# 03_-_CPU_-_SIGNAL_USB_JTAG.net
KiCad netlist of a schematic drawn in Altium Designer
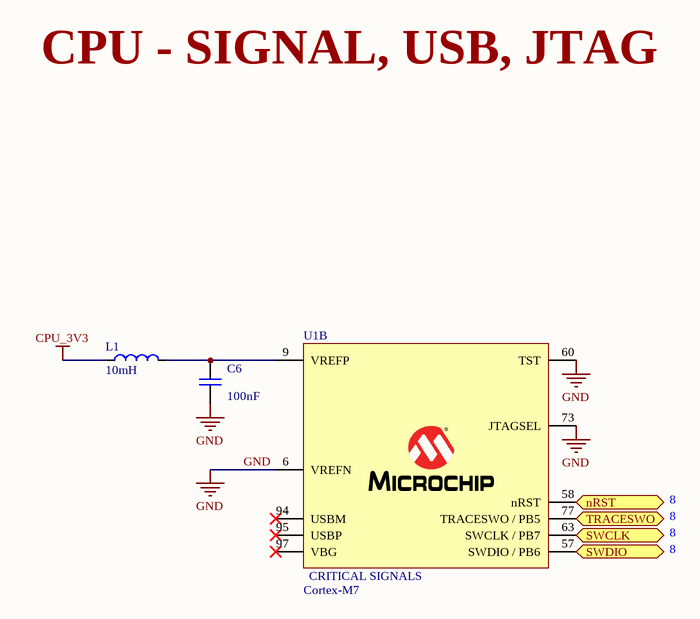
[diagram p0: [03] - CPU - SIGNAL, USB, JTAG.SchDoc]

(export (version "E")
  (design (tool "Eeschema 10.0.6"))
  (components
    (comp (ref "C6")
      (value "100nF")
      (footprint "C0603")
      (description "C0603")
      (fields (field (name "Comment") "02016D104KAT2A"))
      (libsource (lib "Passive components") (part "02016D104KAT2A"))
    )
    (comp (ref "L1")
      (value "10mH")
      (footprint "Inductor 0603")
      (description "Inductor 0603")
      (fields (field (name "Comment") "MLZ1608A2R2WT"))
      (libsource (lib "Passive components") (part "MLZ1608A2R2WT"))
    )
    (comp (ref "U1")
      (value "Cortex-M7")
      (footprint "ATSAMS70N19A-AN")
      (description "ATSAMS70N19")
      (libsource (lib "Microcontrollers") (part "ATSAMS70N19A-AN"))
    )
  )
  (nets
    (net (code "1") (name "/SWCLK") (class "Default")
      (node (ref "U1") (pin "63") (pinfunction "SWCLK_/_PB7_63") (pintype "passive"))
    )
    (net (code "2") (name "/SWDIO") (class "Default")
      (node (ref "U1") (pin "57") (pinfunction "SWDIO_/_PB6_57") (pintype "passive"))
    )
    (net (code "3") (name "/TRACESWO") (class "Default")
      (node (ref "U1") (pin "77") (pinfunction "TRACESWO_/_PB5_77") (pintype "passive"))
    )
    (net (code "4") (name "/nRST") (class "Default")
      (node (ref "U1") (pin "58") (pinfunction "nRST_58") (pintype "passive"))
    )
    (net (code "5") (name "CPU_3V3") (class "Default")
      (node (ref "L1") (pin "1") (pinfunction "1_1") (pintype "passive"))
    )
    (net (code "6") (name "GND") (class "Default")
      (node (ref "C6") (pin "1") (pinfunction "1_1") (pintype "passive"))
      (node (ref "U1") (pin "6") (pinfunction "VREFN_6") (pintype "passive"))
      (node (ref "U1") (pin "60") (pinfunction "TST_60") (pintype "passive"))
      (node (ref "U1") (pin "73") (pinfunction "JTAGSEL_73") (pintype "passive"))
    )
    (net (code "7") (name "Net-(U1B-VREFP)") (class "Default")
      (node (ref "C6") (pin "2") (pinfunction "2_2") (pintype "passive"))
      (node (ref "L1") (pin "2") (pinfunction "2_2") (pintype "passive"))
      (node (ref "U1") (pin "9") (pinfunction "VREFP_9") (pintype "passive"))
    )
    (net (code "8") (name "unconnected-(U1B-USBM-Pad94)") (class "Default")
      (node (ref "U1") (pin "94") (pinfunction "USBM_94") (pintype "passive+no_connect"))
    )
    (net (code "9") (name "unconnected-(U1B-USBP-Pad95)") (class "Default")
      (node (ref "U1") (pin "95") (pinfunction "USBP_95") (pintype "passive+no_connect"))
    )
    (net (code "10") (name "unconnected-(U1B-VBG-Pad97)") (class "Default")
      (node (ref "U1") (pin "97") (pinfunction "VBG_97") (pintype "passive+no_connect"))
    )
  )
)
